# Sheet1.net
KiCad netlist of a schematic drawn in Altium Designer
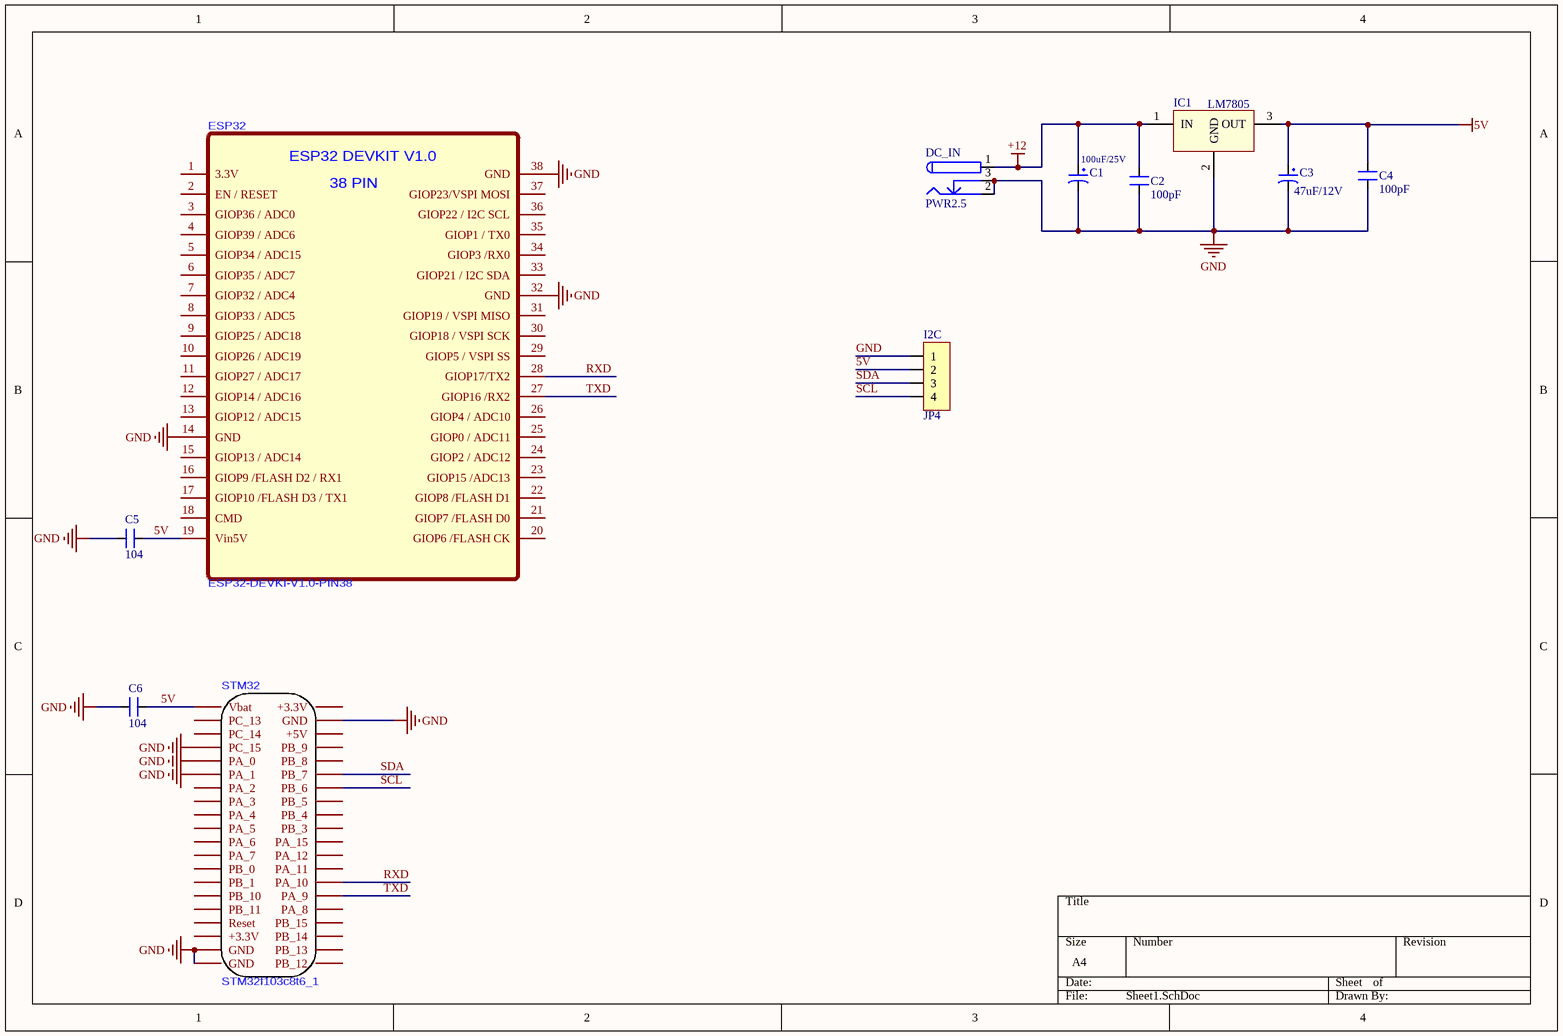
[diagram p0: Sheet1.SchDoc]

(export (version "E")
  (design (tool "Eeschema 10.0.6"))
  (components
    (comp (ref "C1")
      (value "100uF/25V")
      (footprint "CP1.5/3.4")
      (description "Cap 100uF/35V - 470uF/16V")
      (libsource (lib "My Library") (part "CP3"))
    )
    (comp (ref "C2")
      (value "100pF")
      (footprint "CN1")
      (description "Cap np  1pF - 472pF")
      (libsource (lib "My Library") (part "CN1"))
    )
    (comp (ref "C3")
      (value "47uF/12V")
      (footprint "CP1.5/3.4")
      (description "Cap 100uF/35V - 470uF/16V")
      (libsource (lib "My Library") (part "CP3"))
    )
    (comp (ref "C4")
      (value "100pF")
      (footprint "CN1")
      (description "Cap np  1pF - 472pF")
      (libsource (lib "My Library") (part "CN1"))
    )
    (comp (ref "C5")
      (value "104")
      (footprint "CN1")
      (description "Cremic For Xtal 1pF => 100pF")
      (libsource (lib "Altium_Devzone") (part "CAP-DIP"))
    )
    (comp (ref "C6")
      (value "104")
      (footprint "CN1")
      (description "Cremic For Xtal 1pF => 100pF")
      (libsource (lib "Altium_Devzone") (part "CAP-DIP"))
    )
    (comp (ref "DC_IN")
      (value "PWR2.5")
      (footprint "PW-J-2MM")
      (description "Low Voltage Power Supply Connector")
      (fields (field (name "PUBLISHER") "Altium Limited"))
      (libsource (lib "My Library") (part "PWR2.5"))
    )
    (comp (ref "ESP32")
      (value "ESP32-DEVKI-V1.0-PIN38")
      (footprint "ESP32-DEVKIT-V1.0-38PIN-PCB - duplicate")
      (libsource (lib "Schlib1") (part "ESP32-DEVKI-V1.0-PIN38"))
    )
    (comp (ref "I2C")
      (value "JP4")
      (footprint "JP4-C1T")
      (description "WR-PHD 2.54 mm Angled Socket Header")
      (fields
        (field (name "MANUFACTURER") "Würth Elektronik eiSos GmbH")
        (field (name "PARTNO") "613004143121")
        (field (name "CREATED BY") "Karrer Zheng")
      )
      (libsource (lib "My Library") (part "JP4"))
    )
    (comp (ref "IC1")
      (value "LM7805")
      (footprint "QTO-220")
      (description "On ap +, from + 5 to + 24VDC")
      (libsource (lib "My Library") (part "LM78xx"))
    )
    (comp (ref "STM32")
      (value "STM32f103c8t6_1")
      (footprint "STM32F103C8T6")
      (libsource (lib "Altium_Devzone") (part "STM32f103c8t6_1"))
    )
  )
  (nets
    (net (code "1") (name "+12") (class "Default")
      (node (ref "C1") (pin "1") (pinfunction "1_1") (pintype "passive"))
      (node (ref "C2") (pin "2") (pinfunction "2_2") (pintype "passive"))
      (node (ref "DC_IN") (pin "1") (pinfunction "1_1") (pintype "power_in"))
      (node (ref "IC1") (pin "1") (pinfunction "IN_1") (pintype "passive"))
    )
    (net (code "2") (name "/RXD") (class "Default")
      (node (ref "ESP32") (pin "28") (pinfunction "GIOP17/TX2_28") (pintype "passive"))
      (node (ref "STM32") (pin "27") (pinfunction "PA_10_27") (pintype "passive"))
    )
    (net (code "3") (name "/SCL") (class "Default")
      (node (ref "I2C") (pin "4") (pinfunction "4_4") (pintype "passive"))
      (node (ref "STM32") (pin "34") (pinfunction "PB_6_34") (pintype "passive"))
    )
    (net (code "4") (name "/SDA") (class "Default")
      (node (ref "I2C") (pin "3") (pinfunction "3_3") (pintype "passive"))
      (node (ref "STM32") (pin "35") (pinfunction "PB_7_35") (pintype "passive"))
    )
    (net (code "5") (name "/TXD") (class "Default")
      (node (ref "ESP32") (pin "27") (pinfunction "GIOP16_/RX2_27") (pintype "passive"))
      (node (ref "STM32") (pin "26") (pinfunction "PA_9_26") (pintype "passive"))
    )
    (net (code "6") (name "5V") (class "Default")
      (node (ref "C3") (pin "1") (pinfunction "1_1") (pintype "passive"))
      (node (ref "C4") (pin "2") (pinfunction "2_2") (pintype "passive"))
      (node (ref "C5") (pin "2") (pinfunction "2_2") (pintype "passive"))
      (node (ref "C6") (pin "2") (pinfunction "2_2") (pintype "passive"))
      (node (ref "ESP32") (pin "19") (pinfunction "Vin5V_19") (pintype "passive"))
      (node (ref "I2C") (pin "2") (pinfunction "2_2") (pintype "passive"))
      (node (ref "IC1") (pin "3") (pinfunction "OUT_3") (pintype "passive"))
      (node (ref "STM32") (pin "1") (pinfunction "Vbat_1") (pintype "passive"))
    )
    (net (code "7") (name "GND") (class "Default")
      (node (ref "C1") (pin "2") (pinfunction "2_2") (pintype "passive"))
      (node (ref "C2") (pin "1") (pinfunction "1_1") (pintype "passive"))
      (node (ref "C3") (pin "2") (pinfunction "2_2") (pintype "passive"))
      (node (ref "C4") (pin "1") (pinfunction "1_1") (pintype "passive"))
      (node (ref "C5") (pin "1") (pinfunction "1_1") (pintype "passive"))
      (node (ref "C6") (pin "1") (pinfunction "1_1") (pintype "passive"))
      (node (ref "DC_IN") (pin "2") (pinfunction "2_2") (pintype "power_in"))
      (node (ref "DC_IN") (pin "3") (pinfunction "3_3") (pintype "power_in"))
      (node (ref "ESP32") (pin "14") (pinfunction "GND_14") (pintype "passive"))
      (node (ref "ESP32") (pin "32") (pinfunction "GND_32") (pintype "passive"))
      (node (ref "ESP32") (pin "38") (pinfunction "GND_38") (pintype "passive"))
      (node (ref "I2C") (pin "1") (pinfunction "1_1") (pintype "passive"))
      (node (ref "IC1") (pin "2") (pinfunction "GND_2") (pintype "passive"))
      (node (ref "STM32") (pin "19") (pinfunction "GND_19") (pintype "passive"))
      (node (ref "STM32") (pin "20") (pinfunction "GND_20") (pintype "passive"))
      (node (ref "STM32") (pin "39") (pinfunction "GND_39") (pintype "passive"))
      (node (ref "STM32") (pin "4") (pinfunction "PC_15_4") (pintype "passive"))
      (node (ref "STM32") (pin "5") (pinfunction "PA_0_5") (pintype "passive"))
      (node (ref "STM32") (pin "6") (pinfunction "PA_1_6") (pintype "passive"))
    )
    (net (code "8") (name "unconnected-(ESP32-3.3V-Pad1)") (class "Default")
      (node (ref "ESP32") (pin "1") (pinfunction "3.3V_1") (pintype "passive"))
    )
    (net (code "9") (name "unconnected-(ESP32-CMD-Pad18)") (class "Default")
      (node (ref "ESP32") (pin "18") (pinfunction "CMD_18") (pintype "passive"))
    )
    (net (code "10") (name "unconnected-(ESP32-EN_{slash}_RESET-Pad2)") (class "Default")
      (node (ref "ESP32") (pin "2") (pinfunction "EN_/_RESET_2") (pintype "passive"))
    )
    (net (code "11") (name "unconnected-(ESP32-GIOP0_{slash}_ADC11-Pad25)") (class "Default")
      (node (ref "ESP32") (pin "25") (pinfunction "GIOP0_/_ADC11_25") (pintype "passive"))
    )
    (net (code "12") (name "unconnected-(ESP32-GIOP1_{slash}_TX0-Pad35)") (class "Default")
      (node (ref "ESP32") (pin "35") (pinfunction "GIOP1_/_TX0_35") (pintype "passive"))
    )
    (net (code "13") (name "unconnected-(ESP32-GIOP2_{slash}_ADC12-Pad24)") (class "Default")
      (node (ref "ESP32") (pin "24") (pinfunction "GIOP2_/_ADC12_24") (pintype "passive"))
    )
    (net (code "14") (name "unconnected-(ESP32-GIOP3_{slash}RX0-Pad34)") (class "Default")
      (node (ref "ESP32") (pin "34") (pinfunction "GIOP3_/RX0_34") (pintype "passive"))
    )
    (net (code "15") (name "unconnected-(ESP32-GIOP4_{slash}_ADC10-Pad26)") (class "Default")
      (node (ref "ESP32") (pin "26") (pinfunction "GIOP4_/_ADC10_26") (pintype "passive"))
    )
    (net (code "16") (name "unconnected-(ESP32-GIOP5_{slash}_VSPI_SS-Pad29)") (class "Default")
      (node (ref "ESP32") (pin "29") (pinfunction "GIOP5_/_VSPI_SS_29") (pintype "passive"))
    )
    (net (code "17") (name "unconnected-(ESP32-GIOP6_{slash}FLASH_CK-Pad20)") (class "Default")
      (node (ref "ESP32") (pin "20") (pinfunction "GIOP6_/FLASH_CK_20") (pintype "passive"))
    )
    (net (code "18") (name "unconnected-(ESP32-GIOP7_{slash}FLASH_D0-Pad21)") (class "Default")
      (node (ref "ESP32") (pin "21") (pinfunction "GIOP7_/FLASH_D0_21") (pintype "passive"))
    )
    (net (code "19") (name "unconnected-(ESP32-GIOP8_{slash}FLASH_D1-Pad22)") (class "Default")
      (node (ref "ESP32") (pin "22") (pinfunction "GIOP8_/FLASH_D1_22") (pintype "passive"))
    )
    (net (code "20") (name "unconnected-(ESP32-GIOP9_{slash}FLASH_D2_{slash}_RX1-Pad16)") (class "Default")
      (node (ref "ESP32") (pin "16") (pinfunction "GIOP9_/FLASH_D2_/_RX1_16") (pintype "passive"))
    )
    (net (code "21") (name "unconnected-(ESP32-GIOP10_{slash}FLASH_D3_{slash}_TX1-Pad17)") (class "Default")
      (node (ref "ESP32") (pin "17") (pinfunction "GIOP10_/FLASH_D3_/_TX1_17") (pintype "passive"))
    )
    (net (code "22") (name "unconnected-(ESP32-GIOP12_{slash}_ADC15-Pad13)") (class "Default")
      (node (ref "ESP32") (pin "13") (pinfunction "GIOP12_/_ADC15_13") (pintype "passive"))
    )
    (net (code "23") (name "unconnected-(ESP32-GIOP13_{slash}_ADC14-Pad15)") (class "Default")
      (node (ref "ESP32") (pin "15") (pinfunction "GIOP13_/_ADC14_15") (pintype "passive"))
    )
    (net (code "24") (name "unconnected-(ESP32-GIOP14_{slash}_ADC16-Pad12)") (class "Default")
      (node (ref "ESP32") (pin "12") (pinfunction "GIOP14_/_ADC16_12") (pintype "passive"))
    )
    (net (code "25") (name "unconnected-(ESP32-GIOP15_{slash}ADC13-Pad23)") (class "Default")
      (node (ref "ESP32") (pin "23") (pinfunction "GIOP15_/ADC13_23") (pintype "passive"))
    )
    (net (code "26") (name "unconnected-(ESP32-GIOP18_{slash}_VSPI_SCK-Pad30)") (class "Default")
      (node (ref "ESP32") (pin "30") (pinfunction "GIOP18_/_VSPI_SCK_30") (pintype "passive"))
    )
    (net (code "27") (name "unconnected-(ESP32-GIOP19_{slash}_VSPI_MISO-Pad31)") (class "Default")
      (node (ref "ESP32") (pin "31") (pinfunction "GIOP19_/_VSPI_MISO_31") (pintype "passive"))
    )
    (net (code "28") (name "unconnected-(ESP32-GIOP21_{slash}_I2C_SDA-Pad33)") (class "Default")
      (node (ref "ESP32") (pin "33") (pinfunction "GIOP21_/_I2C_SDA_33") (pintype "passive"))
    )
    (net (code "29") (name "unconnected-(ESP32-GIOP22_{slash}_I2C_SCL-Pad36)") (class "Default")
      (node (ref "ESP32") (pin "36") (pinfunction "GIOP22_/_I2C_SCL_36") (pintype "passive"))
    )
    (net (code "30") (name "unconnected-(ESP32-GIOP23{slash}VSPI_MOSI-Pad37)") (class "Default")
      (node (ref "ESP32") (pin "37") (pinfunction "GIOP23/VSPI_MOSI_37") (pintype "passive"))
    )
    (net (code "31") (name "unconnected-(ESP32-GIOP25_{slash}_ADC18-Pad9)") (class "Default")
      (node (ref "ESP32") (pin "9") (pinfunction "GIOP25_/_ADC18_9") (pintype "passive"))
    )
    (net (code "32") (name "unconnected-(ESP32-GIOP26_{slash}_ADC19-Pad10)") (class "Default")
      (node (ref "ESP32") (pin "10") (pinfunction "GIOP26_/_ADC19_10") (pintype "passive"))
    )
    (net (code "33") (name "unconnected-(ESP32-GIOP27_{slash}_ADC17-Pad11)") (class "Default")
      (node (ref "ESP32") (pin "11") (pinfunction "GIOP27_/_ADC17_11") (pintype "passive"))
    )
    (net (code "34") (name "unconnected-(ESP32-GIOP32_{slash}_ADC4-Pad7)") (class "Default")
      (node (ref "ESP32") (pin "7") (pinfunction "GIOP32_/_ADC4_7") (pintype "passive"))
    )
    (net (code "35") (name "unconnected-(ESP32-GIOP33_{slash}_ADC5-Pad8)") (class "Default")
      (node (ref "ESP32") (pin "8") (pinfunction "GIOP33_/_ADC5_8") (pintype "passive"))
    )
    (net (code "36") (name "unconnected-(ESP32-GIOP34_{slash}_ADC15-Pad5)") (class "Default")
      (node (ref "ESP32") (pin "5") (pinfunction "GIOP34_/_ADC15_5") (pintype "passive"))
    )
    (net (code "37") (name "unconnected-(ESP32-GIOP35_{slash}_ADC7-Pad6)") (class "Default")
      (node (ref "ESP32") (pin "6") (pinfunction "GIOP35_/_ADC7_6") (pintype "passive"))
    )
    (net (code "38") (name "unconnected-(ESP32-GIOP36_{slash}_ADC0-Pad3)") (class "Default")
      (node (ref "ESP32") (pin "3") (pinfunction "GIOP36_/_ADC0_3") (pintype "passive"))
    )
    (net (code "39") (name "unconnected-(ESP32-GIOP39_{slash}_ADC6-Pad4)") (class "Default")
      (node (ref "ESP32") (pin "4") (pinfunction "GIOP39_/_ADC6_4") (pintype "passive"))
    )
    (net (code "40") (name "unconnected-(STM32-+3.3V-Pad18)") (class "Default")
      (node (ref "STM32") (pin "18") (pinfunction "+3.3V_18") (pintype "passive"))
    )
    (net (code "41") (name "unconnected-(STM32-+3.3V-Pad40)") (class "Default")
      (node (ref "STM32") (pin "40") (pinfunction "+3.3V_40") (pintype "passive"))
    )
    (net (code "42") (name "unconnected-(STM32-+5V-Pad38)") (class "Default")
      (node (ref "STM32") (pin "38") (pinfunction "+5V_38") (pintype "passive"))
    )
    (net (code "43") (name "unconnected-(STM32-PA_2-Pad7)") (class "Default")
      (node (ref "STM32") (pin "7") (pinfunction "PA_2_7") (pintype "passive"))
    )
    (net (code "44") (name "unconnected-(STM32-PA_3-Pad8)") (class "Default")
      (node (ref "STM32") (pin "8") (pinfunction "PA_3_8") (pintype "passive"))
    )
    (net (code "45") (name "unconnected-(STM32-PA_4-Pad9)") (class "Default")
      (node (ref "STM32") (pin "9") (pinfunction "PA_4_9") (pintype "passive"))
    )
    (net (code "46") (name "unconnected-(STM32-PA_5-Pad10)") (class "Default")
      (node (ref "STM32") (pin "10") (pinfunction "PA_5_10") (pintype "passive"))
    )
    (net (code "47") (name "unconnected-(STM32-PA_6-Pad11)") (class "Default")
      (node (ref "STM32") (pin "11") (pinfunction "PA_6_11") (pintype "passive"))
    )
    (net (code "48") (name "unconnected-(STM32-PA_7-Pad12)") (class "Default")
      (node (ref "STM32") (pin "12") (pinfunction "PA_7_12") (pintype "passive"))
    )
    (net (code "49") (name "unconnected-(STM32-PA_8-Pad25)") (class "Default")
      (node (ref "STM32") (pin "25") (pinfunction "PA_8_25") (pintype "passive"))
    )
    (net (code "50") (name "unconnected-(STM32-PA_11-Pad28)") (class "Default")
      (node (ref "STM32") (pin "28") (pinfunction "PA_11_28") (pintype "passive"))
    )
    (net (code "51") (name "unconnected-(STM32-PA_12-Pad29)") (class "Default")
      (node (ref "STM32") (pin "29") (pinfunction "PA_12_29") (pintype "passive"))
    )
    (net (code "52") (name "unconnected-(STM32-PA_15-Pad30)") (class "Default")
      (node (ref "STM32") (pin "30") (pinfunction "PA_15_30") (pintype "passive"))
    )
    (net (code "53") (name "unconnected-(STM32-PB_0-Pad13)") (class "Default")
      (node (ref "STM32") (pin "13") (pinfunction "PB_0_13") (pintype "passive"))
    )
    (net (code "54") (name "unconnected-(STM32-PB_1-Pad14)") (class "Default")
      (node (ref "STM32") (pin "14") (pinfunction "PB_1_14") (pintype "passive"))
    )
    (net (code "55") (name "unconnected-(STM32-PB_3-Pad31)") (class "Default")
      (node (ref "STM32") (pin "31") (pinfunction "PB_3_31") (pintype "passive"))
    )
    (net (code "56") (name "unconnected-(STM32-PB_4-Pad32)") (class "Default")
      (node (ref "STM32") (pin "32") (pinfunction "PB_4_32") (pintype "passive"))
    )
    (net (code "57") (name "unconnected-(STM32-PB_5-Pad33)") (class "Default")
      (node (ref "STM32") (pin "33") (pinfunction "PB_5_33") (pintype "passive"))
    )
    (net (code "58") (name "unconnected-(STM32-PB_8-Pad36)") (class "Default")
      (node (ref "STM32") (pin "36") (pinfunction "PB_8_36") (pintype "passive"))
    )
    (net (code "59") (name "unconnected-(STM32-PB_9-Pad37)") (class "Default")
      (node (ref "STM32") (pin "37") (pinfunction "PB_9_37") (pintype "passive"))
    )
    (net (code "60") (name "unconnected-(STM32-PB_10-Pad15)") (class "Default")
      (node (ref "STM32") (pin "15") (pinfunction "PB_10_15") (pintype "passive"))
    )
    (net (code "61") (name "unconnected-(STM32-PB_11-Pad16)") (class "Default")
      (node (ref "STM32") (pin "16") (pinfunction "PB_11_16") (pintype "passive"))
    )
    (net (code "62") (name "unconnected-(STM32-PB_12-Pad21)") (class "Default")
      (node (ref "STM32") (pin "21") (pinfunction "PB_12_21") (pintype "passive"))
    )
    (net (code "63") (name "unconnected-(STM32-PB_13-Pad22)") (class "Default")
      (node (ref "STM32") (pin "22") (pinfunction "PB_13_22") (pintype "passive"))
    )
    (net (code "64") (name "unconnected-(STM32-PB_14-Pad23)") (class "Default")
      (node (ref "STM32") (pin "23") (pinfunction "PB_14_23") (pintype "passive"))
    )
    (net (code "65") (name "unconnected-(STM32-PB_15-Pad24)") (class "Default")
      (node (ref "STM32") (pin "24") (pinfunction "PB_15_24") (pintype "passive"))
    )
    (net (code "66") (name "unconnected-(STM32-PC_13-Pad2)") (class "Default")
      (node (ref "STM32") (pin "2") (pinfunction "PC_13_2") (pintype "passive"))
    )
    (net (code "67") (name "unconnected-(STM32-PC_14-Pad3)") (class "Default")
      (node (ref "STM32") (pin "3") (pinfunction "PC_14_3") (pintype "passive"))
    )
    (net (code "68") (name "unconnected-(STM32-Reset-Pad17)") (class "Default")
      (node (ref "STM32") (pin "17") (pinfunction "Reset_17") (pintype "passive"))
    )
  )
)
